# ATTENUATOR_SCH.net
KiCad netlist of a schematic drawn in Altium Designer
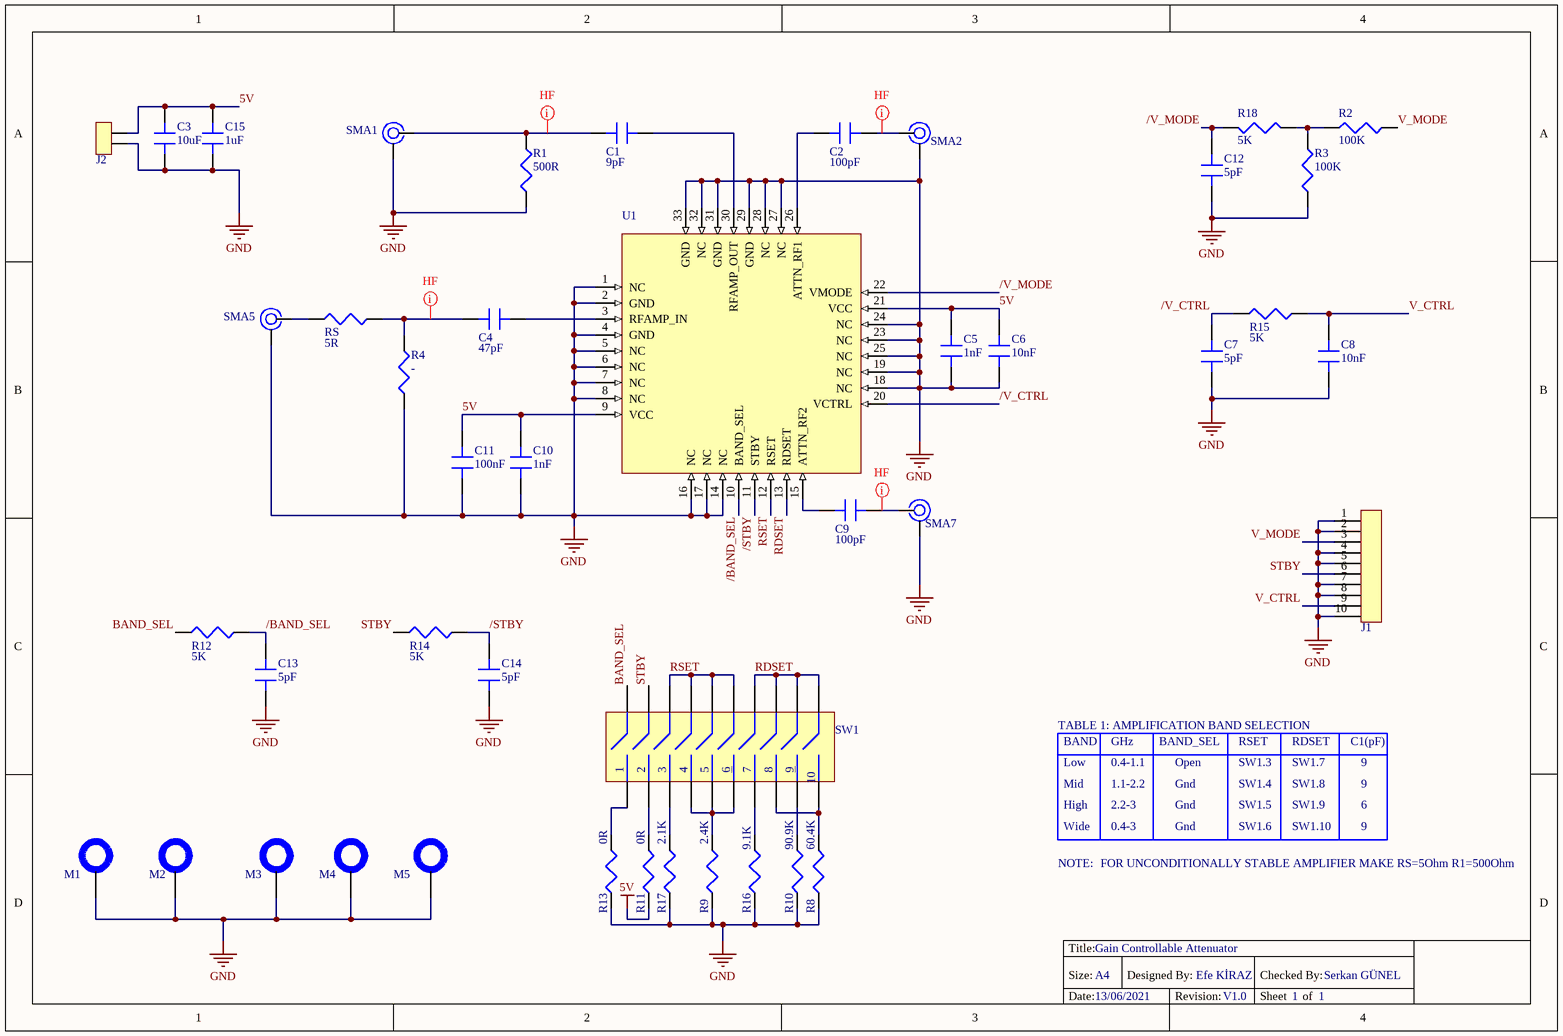
[diagram p0: ATTENUATOR_SCH.SchDoc]

(export (version "E")
  (design (tool "Eeschema 10.0.6"))
  (components
    (comp (ref "C1") (value "9pF") (footprint "C0603") (libsource (lib "pll_schematic_lib") (part "C")))
    (comp (ref "C2") (value "100pF") (footprint "C0603") (libsource (lib "pll_schematic_lib") (part "C")))
    (comp (ref "C3") (value "10uF") (footprint "C_TANT_A") (libsource (lib "pll_schematic_lib") (part "C")))
    (comp (ref "C4") (value "47pF") (footprint "C0603") (libsource (lib "pll_schematic_lib") (part "C")))
    (comp (ref "C5") (value "1nF") (footprint "C0603") (libsource (lib "pll_schematic_lib") (part "C")))
    (comp (ref "C6") (value "10nF") (footprint "C0603") (libsource (lib "pll_schematic_lib") (part "C")))
    (comp (ref "C7") (value "5pF") (footprint "C0603") (libsource (lib "pll_schematic_lib") (part "C")))
    (comp (ref "C8") (value "10nF") (footprint "C0603") (libsource (lib "pll_schematic_lib") (part "C")))
    (comp (ref "C9") (value "100pF") (footprint "C0603") (libsource (lib "pll_schematic_lib") (part "C")))
    (comp (ref "C10") (value "1nF") (footprint "C0603") (libsource (lib "pll_schematic_lib") (part "C")))
    (comp (ref "C11") (value "100nF") (footprint "C0603") (libsource (lib "pll_schematic_lib") (part "C")))
    (comp (ref "C12") (value "5pF") (footprint "C0603") (libsource (lib "pll_schematic_lib") (part "C")))
    (comp (ref "C13") (value "5pF") (footprint "C0603") (libsource (lib "pll_schematic_lib") (part "C")))
    (comp (ref "C14") (value "5pF") (footprint "C0603") (libsource (lib "pll_schematic_lib") (part "C")))
    (comp (ref "C15") (value "1uF") (footprint "C0603") (libsource (lib "pll_schematic_lib") (part "C")))
    (comp (ref "J1")
      (value "-")
      (footprint "IDC-2x05")
      (libsource (lib "pll_schematic_lib") (part "Conn_Gene_1x10"))
    )
    (comp (ref "J2")
      (value "-")
      (footprint "JST_XH_A_2")
      (libsource (lib "pll_schematic_lib") (part "Conn_Gene_1x02"))
    )
    (comp (ref "M1")
      (value "Mounting_Hole_NP")
      (footprint "MOUNTING_HOLE_NP_M3")
      (description "Non-Plated")
      (libsource (lib "pll_schematic_lib") (part "MOUNTING_HOLE"))
    )
    (comp (ref "M2")
      (value "Mounting_Hole_NP")
      (footprint "MOUNTING_HOLE_NP_M3")
      (description "Non-Plated")
      (libsource (lib "pll_schematic_lib") (part "MOUNTING_HOLE"))
    )
    (comp (ref "M3")
      (value "Mounting_Hole_NP")
      (footprint "MOUNTING_HOLE_NP_M3")
      (description "Non-Plated")
      (libsource (lib "pll_schematic_lib") (part "MOUNTING_HOLE"))
    )
    (comp (ref "M4")
      (value "Mounting_Hole_NP")
      (footprint "MOUNTING_HOLE_NP_M3")
      (description "Non-Plated")
      (libsource (lib "pll_schematic_lib") (part "MOUNTING_HOLE"))
    )
    (comp (ref "M5")
      (value "Mounting_Hole_NP")
      (footprint "MOUNTING_HOLE_NP_M3")
      (description "Non-Plated")
      (libsource (lib "pll_schematic_lib") (part "MOUNTING_HOLE"))
    )
    (comp (ref "R1") (value "500R") (footprint "R0603") (libsource (lib "pll_schematic_lib") (part "R")))
    (comp (ref "R2") (value "100K") (footprint "R0603") (libsource (lib "pll_schematic_lib") (part "R")))
    (comp (ref "R3") (value "100K") (footprint "R0603") (libsource (lib "pll_schematic_lib") (part "R")))
    (comp (ref "R4") (value "-") (footprint "R0603") (libsource (lib "pll_schematic_lib") (part "R")))
    (comp (ref "R8") (value "60.4K") (footprint "R0603") (libsource (lib "pll_schematic_lib") (part "R")))
    (comp (ref "R9") (value "2.4K") (footprint "R0603") (libsource (lib "pll_schematic_lib") (part "R")))
    (comp (ref "R10") (value "90.9K") (footprint "R0603") (libsource (lib "pll_schematic_lib") (part "R")))
    (comp (ref "R11") (value "0R") (footprint "R0603") (libsource (lib "pll_schematic_lib") (part "R")))
    (comp (ref "R12") (value "5K") (footprint "R0603") (libsource (lib "pll_schematic_lib") (part "R")))
    (comp (ref "R13") (value "0R") (footprint "R0603") (libsource (lib "pll_schematic_lib") (part "R")))
    (comp (ref "R14") (value "5K") (footprint "R0603") (libsource (lib "pll_schematic_lib") (part "R")))
    (comp (ref "R15") (value "5K") (footprint "R0603") (libsource (lib "pll_schematic_lib") (part "R")))
    (comp (ref "R16") (value "9.1K") (footprint "R0603") (libsource (lib "pll_schematic_lib") (part "R")))
    (comp (ref "R17") (value "2.1K") (footprint "R0603") (libsource (lib "pll_schematic_lib") (part "R")))
    (comp (ref "R18") (value "5K") (footprint "R0603") (libsource (lib "pll_schematic_lib") (part "R")))
    (comp (ref "RS") (value "5R") (footprint "R0603") (libsource (lib "pll_schematic_lib") (part "R")))
    (comp (ref "SMA1") (value "-") (footprint "SMA") (libsource (lib "pll_schematic_lib") (part "SMA")))
    (comp (ref "SMA2") (value "-") (footprint "SMA") (libsource (lib "") (part "SMA_1")))
    (comp (ref "SMA5") (value "-") (footprint "SMA") (libsource (lib "pll_schematic_lib") (part "SMA")))
    (comp (ref "SMA7") (value "-") (footprint "SMA") (libsource (lib "") (part "SMA_1")))
    (comp (ref "SW1")
      (value "DIP SW")
      (footprint "DIP20")
      (libsource (lib "pll_schematic_lib") (part "DIP SW"))
    )
    (comp (ref "U1")
      (value "F2480NBGI")
      (footprint "QFN50P500X500X80_HS-33N_2")
      (libsource (lib "pll_schematic_lib") (part "F2480NBGI"))
    )
  )
  (nets
    (net (code "1") (name "/BAND_SEL") (class "Default")
      (node (ref "R12") (pin "1") (pinfunction "-_1") (pintype "passive"))
      (node (ref "SW1") (pin "1") (pinfunction "*_1") (pintype "passive"))
    )
    (net (code "2") (name "/RDSET") (class "Default")
      (node (ref "SW1") (pin "10") (pinfunction "*_10") (pintype "passive"))
      (node (ref "SW1") (pin "7") (pinfunction "*_7") (pintype "passive"))
      (node (ref "SW1") (pin "8") (pinfunction "*_8") (pintype "passive"))
      (node (ref "SW1") (pin "9") (pinfunction "*_9") (pintype "passive"))
      (node (ref "U1") (pin "13") (pinfunction "RDSET_13") (pintype "input"))
    )
    (net (code "3") (name "/RSET") (class "Default")
      (node (ref "SW1") (pin "3") (pinfunction "*_3") (pintype "passive"))
      (node (ref "SW1") (pin "4") (pinfunction "*_4") (pintype "passive"))
      (node (ref "SW1") (pin "5") (pinfunction "*_5") (pintype "passive"))
      (node (ref "SW1") (pin "6") (pinfunction "*_6") (pintype "passive"))
      (node (ref "U1") (pin "12") (pinfunction "RSET_12") (pintype "input"))
    )
    (net (code "4") (name "/STBY") (class "Default")
      (node (ref "J1") (pin "6") (pinfunction "*_6") (pintype "passive"))
      (node (ref "R14") (pin "1") (pinfunction "-_1") (pintype "passive"))
      (node (ref "SW1") (pin "2") (pinfunction "*_2") (pintype "passive"))
    )
    (net (code "5") (name "/V_CTRL") (class "Default")
      (node (ref "C8") (pin "2") (pinfunction "-_2") (pintype "passive"))
      (node (ref "J1") (pin "9") (pinfunction "*_9") (pintype "passive"))
      (node (ref "R15") (pin "2") (pinfunction "-_2") (pintype "passive"))
    )
    (net (code "6") (name "/V_MODE") (class "Default")
      (node (ref "J1") (pin "3") (pinfunction "*_3") (pintype "passive"))
      (node (ref "R2") (pin "1") (pinfunction "-_1") (pintype "passive"))
    )
    (net (code "7") (name "/{slash}BAND_SEL") (class "Default")
      (node (ref "C13") (pin "1") (pinfunction "-_1") (pintype "passive"))
      (node (ref "R12") (pin "2") (pinfunction "-_2") (pintype "passive"))
      (node (ref "U1") (pin "10") (pinfunction "BAND_SEL_10") (pintype "input"))
    )
    (net (code "8") (name "/{slash}STBY") (class "Default")
      (node (ref "C14") (pin "1") (pinfunction "-_1") (pintype "passive"))
      (node (ref "R14") (pin "2") (pinfunction "-_2") (pintype "passive"))
      (node (ref "U1") (pin "11") (pinfunction "STBY_11") (pintype "input"))
    )
    (net (code "9") (name "/{slash}V_CTRL") (class "Default")
      (node (ref "C7") (pin "1") (pinfunction "-_1") (pintype "passive"))
      (node (ref "R15") (pin "1") (pinfunction "-_1") (pintype "passive"))
      (node (ref "U1") (pin "20") (pinfunction "VCTRL_20") (pintype "input"))
    )
    (net (code "10") (name "/{slash}V_MODE") (class "Default")
      (node (ref "C12") (pin "1") (pinfunction "-_1") (pintype "passive"))
      (node (ref "R18") (pin "1") (pinfunction "-_1") (pintype "passive"))
      (node (ref "U1") (pin "22") (pinfunction "VMODE_22") (pintype "input"))
    )
    (net (code "11") (name "5V") (class "Default")
      (node (ref "C10") (pin "2") (pinfunction "-_2") (pintype "passive"))
      (node (ref "C11") (pin "2") (pinfunction "-_2") (pintype "passive"))
      (node (ref "C15") (pin "1") (pinfunction "-_1") (pintype "passive"))
      (node (ref "C3") (pin "1") (pinfunction "-_1") (pintype "passive"))
      (node (ref "C5") (pin "2") (pinfunction "-_2") (pintype "passive"))
      (node (ref "C6") (pin "2") (pinfunction "-_2") (pintype "passive"))
      (node (ref "J2") (pin "2") (pinfunction "-_2") (pintype "passive"))
      (node (ref "R11") (pin "1") (pinfunction "-_1") (pintype "passive"))
      (node (ref "U1") (pin "21") (pinfunction "VCC_21") (pintype "input"))
      (node (ref "U1") (pin "9") (pinfunction "VCC_9") (pintype "input"))
    )
    (net (code "12") (name "GND") (class "Default")
      (node (ref "C10") (pin "1") (pinfunction "-_1") (pintype "passive"))
      (node (ref "C11") (pin "1") (pinfunction "-_1") (pintype "passive"))
      (node (ref "C12") (pin "2") (pinfunction "-_2") (pintype "passive"))
      (node (ref "C13") (pin "2") (pinfunction "-_2") (pintype "passive"))
      (node (ref "C14") (pin "2") (pinfunction "-_2") (pintype "passive"))
      (node (ref "C15") (pin "2") (pinfunction "-_2") (pintype "passive"))
      (node (ref "C3") (pin "2") (pinfunction "-_2") (pintype "passive"))
      (node (ref "C5") (pin "1") (pinfunction "-_1") (pintype "passive"))
      (node (ref "C6") (pin "1") (pinfunction "-_1") (pintype "passive"))
      (node (ref "C7") (pin "2") (pinfunction "-_2") (pintype "passive"))
      (node (ref "C8") (pin "1") (pinfunction "-_1") (pintype "passive"))
      (node (ref "J1") (pin "1") (pinfunction "*_1") (pintype "passive"))
      (node (ref "J1") (pin "10") (pinfunction "*_10") (pintype "passive"))
      (node (ref "J1") (pin "2") (pinfunction "*_2") (pintype "passive"))
      (node (ref "J1") (pin "4") (pinfunction "*_4") (pintype "passive"))
      (node (ref "J1") (pin "5") (pinfunction "*_5") (pintype "passive"))
      (node (ref "J1") (pin "7") (pinfunction "*_7") (pintype "passive"))
      (node (ref "J1") (pin "8") (pinfunction "*_8") (pintype "passive"))
      (node (ref "J2") (pin "1") (pinfunction "-_1") (pintype "passive"))
      (node (ref "M1") (pin "1") (pinfunction "*_1") (pintype "passive"))
      (node (ref "M2") (pin "1") (pinfunction "*_1") (pintype "passive"))
      (node (ref "M3") (pin "1") (pinfunction "*_1") (pintype "passive"))
      (node (ref "M4") (pin "1") (pinfunction "*_1") (pintype "passive"))
      (node (ref "M5") (pin "1") (pinfunction "*_1") (pintype "passive"))
      (node (ref "R1") (pin "1") (pinfunction "-_1") (pintype "passive"))
      (node (ref "R10") (pin "1") (pinfunction "-_1") (pintype "passive"))
      (node (ref "R13") (pin "1") (pinfunction "-_1") (pintype "passive"))
      (node (ref "R16") (pin "1") (pinfunction "-_1") (pintype "passive"))
      (node (ref "R17") (pin "1") (pinfunction "-_1") (pintype "passive"))
      (node (ref "R3") (pin "1") (pinfunction "-_1") (pintype "passive"))
      (node (ref "R4") (pin "1") (pinfunction "-_1") (pintype "passive"))
      (node (ref "R8") (pin "1") (pinfunction "-_1") (pintype "passive"))
      (node (ref "R9") (pin "1") (pinfunction "-_1") (pintype "passive"))
      (node (ref "SMA1") (pin "2") (pinfunction "-_2") (pintype "passive"))
      (node (ref "SMA2") (pin "2") (pinfunction "-_2") (pintype "passive"))
      (node (ref "SMA5") (pin "2") (pinfunction "-_2") (pintype "passive"))
      (node (ref "SMA7") (pin "2") (pinfunction "-_2") (pintype "passive"))
      (node (ref "U1") (pin "1") (pinfunction "NC_1") (pintype "input"))
      (node (ref "U1") (pin "14") (pinfunction "NC_14") (pintype "input"))
      (node (ref "U1") (pin "16") (pinfunction "NC_16") (pintype "input"))
      (node (ref "U1") (pin "17") (pinfunction "NC_17") (pintype "input"))
      (node (ref "U1") (pin "18") (pinfunction "NC_18") (pintype "input"))
      (node (ref "U1") (pin "19") (pinfunction "NC_19") (pintype "input"))
      (node (ref "U1") (pin "2") (pinfunction "GND_2") (pintype "input"))
      (node (ref "U1") (pin "23") (pinfunction "NC_23") (pintype "input"))
      (node (ref "U1") (pin "24") (pinfunction "NC_24") (pintype "input"))
      (node (ref "U1") (pin "25") (pinfunction "NC_25") (pintype "input"))
      (node (ref "U1") (pin "27") (pinfunction "NC_27") (pintype "input"))
      (node (ref "U1") (pin "28") (pinfunction "NC_28") (pintype "input"))
      (node (ref "U1") (pin "29") (pinfunction "GND_29") (pintype "input"))
      (node (ref "U1") (pin "31") (pinfunction "GND_31") (pintype "input"))
      (node (ref "U1") (pin "32") (pinfunction "NC_32") (pintype "input"))
      (node (ref "U1") (pin "33") (pinfunction "GND_33") (pintype "input"))
      (node (ref "U1") (pin "4") (pinfunction "GND_4") (pintype "input"))
      (node (ref "U1") (pin "5") (pinfunction "NC_5") (pintype "input"))
      (node (ref "U1") (pin "6") (pinfunction "NC_6") (pintype "input"))
      (node (ref "U1") (pin "7") (pinfunction "NC_7") (pintype "input"))
      (node (ref "U1") (pin "8") (pinfunction "NC_8") (pintype "input"))
    )
    (net (code "13") (name "Net-(C1---Pad1)") (class "Default")
      (node (ref "C1") (pin "1") (pinfunction "-_1") (pintype "passive"))
      (node (ref "R1") (pin "2") (pinfunction "-_2") (pintype "passive"))
      (node (ref "SMA1") (pin "1") (pinfunction "-_1") (pintype "passive"))
    )
    (net (code "14") (name "Net-(C2---Pad2)") (class "Default")
      (node (ref "C2") (pin "2") (pinfunction "-_2") (pintype "passive"))
      (node (ref "SMA2") (pin "1") (pinfunction "-_1") (pintype "passive"))
    )
    (net (code "15") (name "Net-(C4---Pad1)") (class "Default")
      (node (ref "C4") (pin "1") (pinfunction "-_1") (pintype "passive"))
      (node (ref "R4") (pin "2") (pinfunction "-_2") (pintype "passive"))
      (node (ref "RS") (pin "2") (pinfunction "-_2") (pintype "passive"))
    )
    (net (code "16") (name "Net-(C9---Pad2)") (class "Default")
      (node (ref "C9") (pin "2") (pinfunction "-_2") (pintype "passive"))
      (node (ref "SMA7") (pin "1") (pinfunction "-_1") (pintype "passive"))
    )
    (net (code "17") (name "Net-(R8---Pad2)") (class "Default")
      (node (ref "R8") (pin "2") (pinfunction "-_2") (pintype "passive"))
      (node (ref "SW1") (pin "11") (pinfunction "*_11") (pintype "passive"))
      (node (ref "SW1") (pin "13") (pinfunction "*_13") (pintype "passive"))
    )
    (net (code "18") (name "Net-(R9---Pad2)") (class "Default")
      (node (ref "R9") (pin "2") (pinfunction "-_2") (pintype "passive"))
      (node (ref "SW1") (pin "15") (pinfunction "*_15") (pintype "passive"))
      (node (ref "SW1") (pin "16") (pinfunction "*_16") (pintype "passive"))
      (node (ref "SW1") (pin "17") (pinfunction "*_17") (pintype "passive"))
    )
    (net (code "19") (name "Net-(R10---Pad2)") (class "Default")
      (node (ref "R10") (pin "2") (pinfunction "-_2") (pintype "passive"))
      (node (ref "SW1") (pin "12") (pinfunction "*_12") (pintype "passive"))
    )
    (net (code "20") (name "Net-(R11---Pad2)") (class "Default")
      (node (ref "R11") (pin "2") (pinfunction "-_2") (pintype "passive"))
      (node (ref "SW1") (pin "19") (pinfunction "*_19") (pintype "passive"))
    )
    (net (code "21") (name "Net-(R13---Pad2)") (class "Default")
      (node (ref "R13") (pin "2") (pinfunction "-_2") (pintype "passive"))
      (node (ref "SW1") (pin "20") (pinfunction "*_20") (pintype "passive"))
    )
    (net (code "22") (name "Net-(R16---Pad2)") (class "Default")
      (node (ref "R16") (pin "2") (pinfunction "-_2") (pintype "passive"))
      (node (ref "SW1") (pin "14") (pinfunction "*_14") (pintype "passive"))
    )
    (net (code "23") (name "Net-(R17---Pad2)") (class "Default")
      (node (ref "R17") (pin "2") (pinfunction "-_2") (pintype "passive"))
      (node (ref "SW1") (pin "18") (pinfunction "*_18") (pintype "passive"))
    )
    (net (code "24") (name "Net-(R18---Pad2)") (class "Default")
      (node (ref "R18") (pin "2") (pinfunction "-_2") (pintype "passive"))
      (node (ref "R2") (pin "2") (pinfunction "-_2") (pintype "passive"))
      (node (ref "R3") (pin "2") (pinfunction "-_2") (pintype "passive"))
    )
    (net (code "25") (name "Net-(RS---Pad1)") (class "Default")
      (node (ref "RS") (pin "1") (pinfunction "-_1") (pintype "passive"))
      (node (ref "SMA5") (pin "1") (pinfunction "-_1") (pintype "passive"))
    )
    (net (code "26") (name "Net-(U1-ATTN_RF1)") (class "Default")
      (node (ref "C2") (pin "1") (pinfunction "-_1") (pintype "passive"))
      (node (ref "U1") (pin "26") (pinfunction "ATTN_RF1_26") (pintype "input"))
    )
    (net (code "27") (name "Net-(U1-ATTN_RF2)") (class "Default")
      (node (ref "C9") (pin "1") (pinfunction "-_1") (pintype "passive"))
      (node (ref "U1") (pin "15") (pinfunction "ATTN_RF2_15") (pintype "input"))
    )
    (net (code "28") (name "Net-(U1-RFAMP_IN)") (class "Default")
      (node (ref "C4") (pin "2") (pinfunction "-_2") (pintype "passive"))
      (node (ref "U1") (pin "3") (pinfunction "RFAMP_IN_3") (pintype "input"))
    )
    (net (code "29") (name "Net-(U1-RFAMP_OUT)") (class "Default")
      (node (ref "C1") (pin "2") (pinfunction "-_2") (pintype "passive"))
      (node (ref "U1") (pin "30") (pinfunction "RFAMP_OUT_30") (pintype "input"))
    )
  )
)
